# esq.net
KiCad netlist of a schematic drawn in Altium Designer
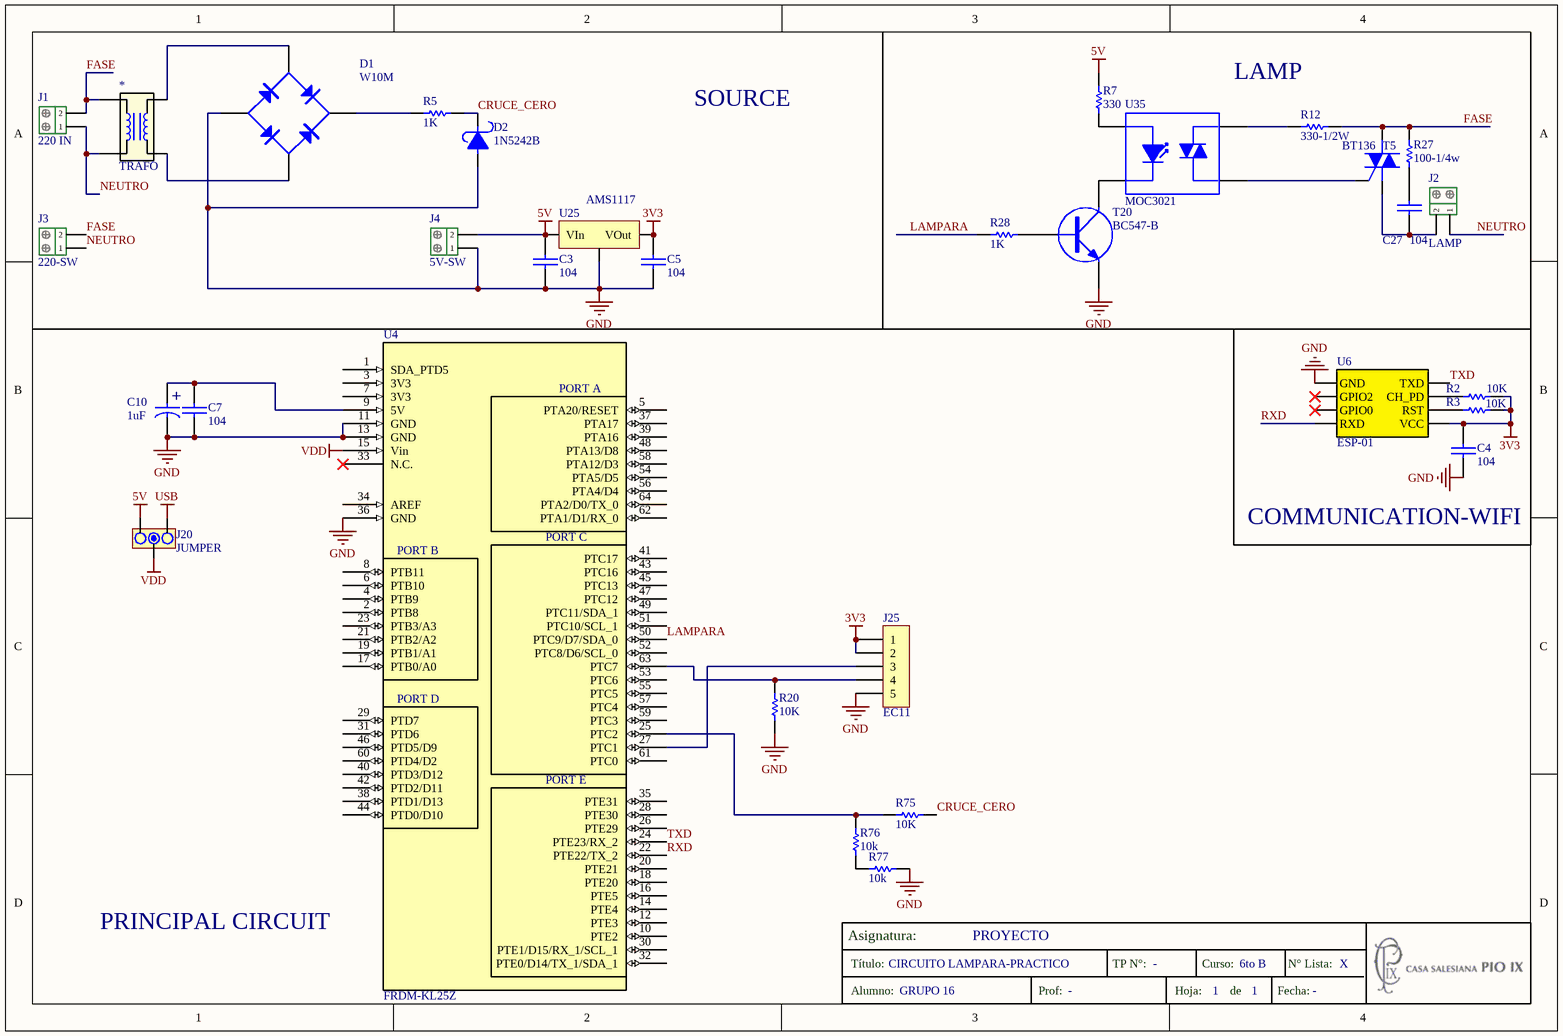
[diagram p0: esq.SchDoc]

(export (version "E")
  (design (tool "Eeschema 10.0.6"))
  (components
    (comp (ref "*") (value "TRAFO") (footprint "trafo") (libsource (lib "Schlib1") (part "TRAFO")))
    (comp (ref "C3")
      (value "104")
      (footprint "0805")
      (description "cap")
      (fields (field (name "AUTOR") "Guido Spataro"))
      (libsource (lib "Schlib1") (part "CAP"))
    )
    (comp (ref "C4")
      (value "104")
      (footprint "0805")
      (description "cap")
      (fields (field (name "AUTOR") "Guido Spataro"))
      (libsource (lib "scdlib") (part "CAP"))
    )
    (comp (ref "C5")
      (value "104")
      (footprint "0805")
      (description "cap")
      (fields (field (name "AUTOR") "Guido Spataro"))
      (libsource (lib "Schlib1") (part "CAP"))
    )
    (comp (ref "C7")
      (value "104")
      (footprint "0805")
      (description "cap")
      (fields (field (name "AUTOR") "Guido Spataro"))
      (libsource (lib "scdlib") (part "CAP"))
    )
    (comp (ref "C10")
      (value "1uF")
      (footprint "CAP100RP")
      (description "Cap polarizado")
      (libsource (lib "Schlib1") (part "CAPPOL"))
    )
    (comp (ref "C27")
      (value "104")
      (footprint "0805")
      (description "cap")
      (fields (field (name "AUTOR") "Guido Spataro"))
      (libsource (lib "Schlib1") (part "CAP"))
    )
    (comp (ref "D1") (value "W10M") (footprint "PUENTE - W10M") (libsource (lib "Schlib1") (part "PUENTE")))
    (comp (ref "D2")
      (value "1N5242B")
      (footprint "Diodo")
      (description "Diodo")
      (fields (field (name "AUTOR") "Guido Spataro"))
      (libsource (lib "Schlib1") (part "DIODO SCHOTTKY"))
    )
    (comp (ref "J1")
      (value "220 IN")
      (footprint "BORNERA2")
      (description "Bornera de 2 pines")
      (fields (field (name "AUTOR") "Guido Spataro"))
      (libsource (lib "Schlib1") (part "Bornera_2"))
    )
    (comp (ref "J2")
      (value "LAMP")
      (footprint "BORNERA2")
      (description "Bornera de 2 pines")
      (fields (field (name "AUTOR") "Guido Spataro"))
      (libsource (lib "") (part "Bornera_2_1"))
    )
    (comp (ref "J3")
      (value "220-SW")
      (footprint "BORNERA2")
      (description "Bornera de 2 pines")
      (fields (field (name "AUTOR") "Guido Spataro"))
      (libsource (lib "Schlib1") (part "Bornera_2"))
    )
    (comp (ref "J4")
      (value "5V-SW")
      (footprint "BORNERA2")
      (description "Bornera de 2 pines")
      (fields (field (name "AUTOR") "Guido Spataro"))
      (libsource (lib "Schlib1") (part "Bornera_2"))
    )
    (comp (ref "J20") (value "JUMPER") (footprint "JUMPER3") (libsource (lib "scdlib") (part "JUMPER3")))
    (comp (ref "J25") (value "EC11") (footprint "BORNERA5") (libsource (lib "Schlib1") (part "BORNERA 5")))
    (comp (ref "R2")
      (value "10K")
      (footprint "0805")
      (description "Resistencia")
      (fields (field (name "AUTOR") "Guido Spataro"))
      (libsource (lib "scdlib") (part "RES"))
    )
    (comp (ref "R3")
      (value "10K")
      (footprint "0805")
      (description "Resistencia")
      (fields (field (name "AUTOR") "Guido Spataro"))
      (libsource (lib "scdlib") (part "RES"))
    )
    (comp (ref "R5")
      (value "1K")
      (footprint "0805")
      (description "Resistencia")
      (fields (field (name "AUTOR") "Guido Spataro"))
      (libsource (lib "Schlib1") (part "RES"))
    )
    (comp (ref "R7")
      (value "330")
      (footprint "0805")
      (description "Resistencia")
      (fields (field (name "AUTOR") "Guido Spataro"))
      (libsource (lib "Schlib1") (part "RES"))
    )
    (comp (ref "R12")
      (value "330-1/2W")
      (footprint "RES500")
      (description "Resistencia")
      (fields (field (name "AUTOR") "Guido Spataro"))
      (libsource (lib "Schlib1") (part "RES"))
    )
    (comp (ref "R20")
      (value "10K")
      (footprint "0805")
      (description "Resistencia")
      (fields (field (name "AUTOR") "Guido Spataro"))
      (libsource (lib "Schlib1") (part "RES"))
    )
    (comp (ref "R27")
      (value "100-1/4w")
      (footprint "RES400")
      (description "Resistencia")
      (fields (field (name "AUTOR") "Guido Spataro"))
      (libsource (lib "Schlib1") (part "RES"))
    )
    (comp (ref "R28")
      (value "1K")
      (footprint "0805")
      (description "Resistencia")
      (fields (field (name "AUTOR") "Guido Spataro"))
      (libsource (lib "Schlib1") (part "RES"))
    )
    (comp (ref "R75")
      (value "10K")
      (footprint "0805")
      (description "Resistencia")
      (fields (field (name "AUTOR") "Guido Spataro"))
      (libsource (lib "Schlib1") (part "RES"))
    )
    (comp (ref "R76")
      (value "10k")
      (footprint "0805")
      (description "Resistencia")
      (fields (field (name "AUTOR") "Guido Spataro"))
      (libsource (lib "Schlib1") (part "RES"))
    )
    (comp (ref "R77")
      (value "10k")
      (footprint "0805")
      (description "Resistencia")
      (fields (field (name "AUTOR") "Guido Spataro"))
      (libsource (lib "Schlib1") (part "RES"))
    )
    (comp (ref "T5") (value "BT136") (footprint "BT136") (libsource (lib "Schlib1") (part "BT136")))
    (comp (ref "T20")
      (value "BC547-B")
      (footprint "SOT23")
      (libsource (lib "Schlib1") (part "TRANSISTOR NPN"))
    )
    (comp (ref "U4")
      (value "FRDM-KL25Z")
      (footprint "MICRO")
      (fields (field (name "AUTOR") "Guido Spataro"))
      (libsource (lib "Schlib1") (part "FRDM-KL25Z"))
    )
    (comp (ref "U6") (value "ESP-01") (footprint "ESP-01") (libsource (lib "Schlib1") (part "ESP-01")))
    (comp (ref "U25") (value "AMS1117") (footprint "AMS1117") (libsource (lib "Schlib1") (part "AMS1117")))
    (comp (ref "U35")
      (value "MOC3021")
      (footprint "MOC3021")
      (description "OPTO-ACOPLADOR")
      (libsource (lib "Schlib1") (part "MOC3021"))
    )
  )
  (nets
    (net (code "1") (name "/CRUCE_CERO") (class "Default")
      (node (ref "D2") (pin "2") (pinfunction "2_2") (pintype "passive"))
      (node (ref "R5") (pin "2") (pinfunction "2_2") (pintype "passive"))
      (node (ref "R75") (pin "1") (pinfunction "1_1") (pintype "passive"))
    )
    (net (code "2") (name "/FASE") (class "Default")
      (node (ref "*") (pin "1") (pinfunction "1_1") (pintype "passive"))
      (node (ref "J1") (pin "2") (pinfunction "2_2") (pintype "passive"))
      (node (ref "J3") (pin "2") (pinfunction "2_2") (pintype "passive"))
      (node (ref "R12") (pin "2") (pinfunction "2_2") (pintype "passive"))
      (node (ref "R27") (pin "2") (pinfunction "2_2") (pintype "passive"))
      (node (ref "T5") (pin "2") (pinfunction "M2_2") (pintype "passive"))
    )
    (net (code "3") (name "/LAMPARA") (class "Default")
      (node (ref "R28") (pin "1") (pinfunction "1_1") (pintype "passive"))
      (node (ref "U4") (pin "50") (pinfunction "PTC9/D7/SDA_0_50") (pintype "bidirectional"))
    )
    (net (code "4") (name "/NEUTRO") (class "Default")
      (node (ref "*") (pin "5") (pinfunction "5_5") (pintype "passive"))
      (node (ref "J1") (pin "1") (pinfunction "1_1") (pintype "passive"))
      (node (ref "J2") (pin "1") (pinfunction "1_1") (pintype "passive"))
      (node (ref "J3") (pin "1") (pinfunction "1_1") (pintype "passive"))
    )
    (net (code "5") (name "/RXD") (class "Default")
      (node (ref "U4") (pin "22") (pinfunction "PTE22/TX_2_22") (pintype "bidirectional"))
      (node (ref "U6") (pin "4") (pinfunction "RXD_4") (pintype "passive"))
    )
    (net (code "6") (name "/TXD") (class "Default")
      (node (ref "U4") (pin "24") (pinfunction "PTE23/RX_2_24") (pintype "bidirectional"))
      (node (ref "U6") (pin "5") (pinfunction "TXD_5") (pintype "passive"))
    )
    (net (code "7") (name "3V3") (class "Default")
      (node (ref "C4") (pin "2") (pinfunction "2_2") (pintype "passive"))
      (node (ref "C5") (pin "1") (pinfunction "1_1") (pintype "passive"))
      (node (ref "J25") (pin "1") (pinfunction "1_1") (pintype "passive"))
      (node (ref "J25") (pin "2") (pinfunction "2_2") (pintype "passive"))
      (node (ref "R2") (pin "1") (pinfunction "1_1") (pintype "passive"))
      (node (ref "R3") (pin "1") (pinfunction "1_1") (pintype "passive"))
      (node (ref "U25") (pin "3") (pinfunction "VOut_3") (pintype "passive"))
      (node (ref "U6") (pin "8") (pinfunction "VCC_8") (pintype "passive"))
    )
    (net (code "8") (name "5V") (class "Default")
      (node (ref "C3") (pin "1") (pinfunction "1_1") (pintype "passive"))
      (node (ref "J20") (pin "1") (pinfunction "1_1") (pintype "passive"))
      (node (ref "J4") (pin "2") (pinfunction "2_2") (pintype "passive"))
      (node (ref "R7") (pin "1") (pinfunction "1_1") (pintype "passive"))
      (node (ref "U25") (pin "1") (pinfunction "VIn_1") (pintype "passive"))
    )
    (net (code "9") (name "GND") (class "Default")
      (node (ref "C10") (pin "2") (pinfunction "2_2") (pintype "passive"))
      (node (ref "C3") (pin "2") (pinfunction "2_2") (pintype "passive"))
      (node (ref "C4") (pin "1") (pinfunction "1_1") (pintype "passive"))
      (node (ref "C5") (pin "2") (pinfunction "2_2") (pintype "passive"))
      (node (ref "C7") (pin "1") (pinfunction "1_1") (pintype "passive"))
      (node (ref "D1") (pin "3") (pinfunction "V-_3") (pintype "passive"))
      (node (ref "D2") (pin "1") (pinfunction "1_1") (pintype "passive"))
      (node (ref "J25") (pin "5") (pinfunction "5_5") (pintype "passive"))
      (node (ref "J4") (pin "1") (pinfunction "1_1") (pintype "passive"))
      (node (ref "R20") (pin "1") (pinfunction "1_1") (pintype "passive"))
      (node (ref "R77") (pin "1") (pinfunction "1_1") (pintype "passive"))
      (node (ref "T20") (pin "3") (pinfunction "E_3") (pintype "passive"))
      (node (ref "U25") (pin "2") (pinfunction "GND_2") (pintype "passive"))
      (node (ref "U4") (pin "11") (pinfunction "GND_11") (pintype "input"))
      (node (ref "U4") (pin "13") (pinfunction "GND_13") (pintype "input"))
      (node (ref "U4") (pin "36") (pinfunction "GND_36") (pintype "input"))
      (node (ref "U6") (pin "1") (pinfunction "GND_1") (pintype "passive"))
    )
    (net (code "10") (name "Net-(*-Pad7)") (class "Default")
      (node (ref "*") (pin "7") (pinfunction "7_7") (pintype "passive"))
      (node (ref "D1") (pin "2") (pinfunction "AC_2") (pintype "passive"))
    )
    (net (code "11") (name "Net-(*-Pad9)") (class "Default")
      (node (ref "*") (pin "9") (pinfunction "9_9") (pintype "passive"))
      (node (ref "D1") (pin "4") (pinfunction "AC_4") (pintype "passive"))
    )
    (net (code "12") (name "Net-(C27-Pad1)") (class "Default")
      (node (ref "C27") (pin "1") (pinfunction "1_1") (pintype "passive"))
      (node (ref "R27") (pin "1") (pinfunction "1_1") (pintype "passive"))
    )
    (net (code "13") (name "Net-(D1-V+)") (class "Default")
      (node (ref "D1") (pin "1") (pinfunction "V+_1") (pintype "passive"))
      (node (ref "R5") (pin "1") (pinfunction "1_1") (pintype "passive"))
    )
    (net (code "14") (name "Net-(R76-Pad1)") (class "Default")
      (node (ref "R76") (pin "1") (pinfunction "1_1") (pintype "passive"))
      (node (ref "R77") (pin "2") (pinfunction "2_2") (pintype "passive"))
    )
    (net (code "15") (name "Net-(T5-G)") (class "Default")
      (node (ref "T5") (pin "3") (pinfunction "G_3") (pintype "passive"))
      (node (ref "U35") (pin "4") (pinfunction "E_4") (pintype "passive"))
    )
    (net (code "16") (name "Net-(T5-M1)") (class "Default")
      (node (ref "C27") (pin "2") (pinfunction "2_2") (pintype "passive"))
      (node (ref "J2") (pin "2") (pinfunction "2_2") (pintype "passive"))
      (node (ref "T5") (pin "1") (pinfunction "M1_1") (pintype "passive"))
    )
    (net (code "17") (name "Net-(T20-B)") (class "Default")
      (node (ref "R28") (pin "2") (pinfunction "2_2") (pintype "passive"))
      (node (ref "T20") (pin "1") (pinfunction "B_1") (pintype "passive"))
    )
    (net (code "18") (name "Net-(T20-C)") (class "Default")
      (node (ref "T20") (pin "2") (pinfunction "C_2") (pintype "passive"))
      (node (ref "U35") (pin "2") (pinfunction "K_2") (pintype "passive"))
    )
    (net (code "19") (name "Net-(U4-5V)") (class "Default")
      (node (ref "C10") (pin "1") (pinfunction "1_1") (pintype "passive"))
      (node (ref "C7") (pin "2") (pinfunction "2_2") (pintype "passive"))
      (node (ref "U4") (pin "9") (pinfunction "5V_9") (pintype "input"))
    )
    (net (code "20") (name "Net-(U4-PTC1)") (class "Default")
      (node (ref "J25") (pin "3") (pinfunction "3_3") (pintype "passive"))
      (node (ref "U4") (pin "27") (pinfunction "PTC1_27") (pintype "bidirectional"))
    )
    (net (code "21") (name "Net-(U4-PTC2)") (class "Default")
      (node (ref "R75") (pin "2") (pinfunction "2_2") (pintype "passive"))
      (node (ref "R76") (pin "2") (pinfunction "2_2") (pintype "passive"))
      (node (ref "U4") (pin "25") (pinfunction "PTC2_25") (pintype "bidirectional"))
    )
    (net (code "22") (name "Net-(U4-PTC7)") (class "Default")
      (node (ref "J25") (pin "4") (pinfunction "4_4") (pintype "passive"))
      (node (ref "R20") (pin "2") (pinfunction "2_2") (pintype "passive"))
      (node (ref "U4") (pin "63") (pinfunction "PTC7_63") (pintype "bidirectional"))
    )
    (net (code "23") (name "Net-(U6-CH_PD)") (class "Default")
      (node (ref "R2") (pin "2") (pinfunction "2_2") (pintype "passive"))
      (node (ref "U6") (pin "6") (pinfunction "CH_PD_6") (pintype "passive"))
    )
    (net (code "24") (name "Net-(U6-RST)") (class "Default")
      (node (ref "R3") (pin "2") (pinfunction "2_2") (pintype "passive"))
      (node (ref "U6") (pin "7") (pinfunction "RST_7") (pintype "passive"))
    )
    (net (code "25") (name "Net-(U35-A)") (class "Default")
      (node (ref "R7") (pin "2") (pinfunction "2_2") (pintype "passive"))
      (node (ref "U35") (pin "1") (pinfunction "A_1") (pintype "passive"))
    )
    (net (code "26") (name "Net-(U35-C)") (class "Default")
      (node (ref "R12") (pin "1") (pinfunction "1_1") (pintype "passive"))
      (node (ref "U35") (pin "6") (pinfunction "C_6") (pintype "passive"))
    )
    (net (code "27") (name "USB") (class "Default")
      (node (ref "J20") (pin "3") (pinfunction "3_3") (pintype "passive"))
    )
    (net (code "28") (name "VDD") (class "Default")
      (node (ref "J20") (pin "2") (pinfunction "2_2") (pintype "passive"))
      (node (ref "U4") (pin "15") (pinfunction "Vin_15") (pintype "input"))
    )
    (net (code "29") (name "unconnected-(U4-3V3-Pad3)") (class "Default")
      (node (ref "U4") (pin "3") (pinfunction "3V3_3") (pintype "input"))
    )
    (net (code "30") (name "unconnected-(U4-3V3-Pad7)") (class "Default")
      (node (ref "U4") (pin "7") (pinfunction "3V3_7") (pintype "input"))
    )
    (net (code "31") (name "unconnected-(U4-AREF-Pad34)") (class "Default")
      (node (ref "U4") (pin "34") (pinfunction "AREF_34") (pintype "input"))
    )
    (net (code "32") (name "unconnected-(U4-N.C.-Pad33)") (class "Default")
      (node (ref "U4") (pin "33") (pinfunction "N.C._33") (pintype "open_emitter+no_connect"))
    )
    (net (code "33") (name "unconnected-(U4-PTA1{slash}D1{slash}RX_0-Pad62)") (class "Default")
      (node (ref "U4") (pin "62") (pinfunction "PTA1/D1/RX_0_62") (pintype "bidirectional"))
    )
    (net (code "34") (name "unconnected-(U4-PTA2{slash}D0{slash}TX_0-Pad64)") (class "Default")
      (node (ref "U4") (pin "64") (pinfunction "PTA2/D0/TX_0_64") (pintype "bidirectional"))
    )
    (net (code "35") (name "unconnected-(U4-PTA4{slash}D4-Pad56)") (class "Default")
      (node (ref "U4") (pin "56") (pinfunction "PTA4/D4_56") (pintype "bidirectional"))
    )
    (net (code "36") (name "unconnected-(U4-PTA5{slash}D5-Pad54)") (class "Default")
      (node (ref "U4") (pin "54") (pinfunction "PTA5/D5_54") (pintype "bidirectional"))
    )
    (net (code "37") (name "unconnected-(U4-PTA12{slash}D3-Pad58)") (class "Default")
      (node (ref "U4") (pin "58") (pinfunction "PTA12/D3_58") (pintype "bidirectional"))
    )
    (net (code "38") (name "unconnected-(U4-PTA13{slash}D8-Pad48)") (class "Default")
      (node (ref "U4") (pin "48") (pinfunction "PTA13/D8_48") (pintype "bidirectional"))
    )
    (net (code "39") (name "unconnected-(U4-PTA16-Pad39)") (class "Default")
      (node (ref "U4") (pin "39") (pinfunction "PTA16_39") (pintype "bidirectional"))
    )
    (net (code "40") (name "unconnected-(U4-PTA17-Pad37)") (class "Default")
      (node (ref "U4") (pin "37") (pinfunction "PTA17_37") (pintype "bidirectional"))
    )
    (net (code "41") (name "unconnected-(U4-PTA20{slash}RESET-Pad5)") (class "Default")
      (node (ref "U4") (pin "5") (pinfunction "PTA20/RESET_5") (pintype "bidirectional"))
    )
    (net (code "42") (name "unconnected-(U4-PTB0{slash}A0-Pad17)") (class "Default")
      (node (ref "U4") (pin "17") (pinfunction "PTB0/A0_17") (pintype "bidirectional"))
    )
    (net (code "43") (name "unconnected-(U4-PTB1{slash}A1-Pad19)") (class "Default")
      (node (ref "U4") (pin "19") (pinfunction "PTB1/A1_19") (pintype "bidirectional"))
    )
    (net (code "44") (name "unconnected-(U4-PTB2{slash}A2-Pad21)") (class "Default")
      (node (ref "U4") (pin "21") (pinfunction "PTB2/A2_21") (pintype "bidirectional"))
    )
    (net (code "45") (name "unconnected-(U4-PTB3{slash}A3-Pad23)") (class "Default")
      (node (ref "U4") (pin "23") (pinfunction "PTB3/A3_23") (pintype "bidirectional"))
    )
    (net (code "46") (name "unconnected-(U4-PTB8-Pad2)") (class "Default")
      (node (ref "U4") (pin "2") (pinfunction "PTB8_2") (pintype "bidirectional"))
    )
    (net (code "47") (name "unconnected-(U4-PTB9-Pad4)") (class "Default")
      (node (ref "U4") (pin "4") (pinfunction "PTB9_4") (pintype "bidirectional"))
    )
    (net (code "48") (name "unconnected-(U4-PTB10-Pad6)") (class "Default")
      (node (ref "U4") (pin "6") (pinfunction "PTB10_6") (pintype "bidirectional"))
    )
    (net (code "49") (name "unconnected-(U4-PTB11-Pad8)") (class "Default")
      (node (ref "U4") (pin "8") (pinfunction "PTB11_8") (pintype "bidirectional"))
    )
    (net (code "50") (name "unconnected-(U4-PTC0-Pad61)") (class "Default")
      (node (ref "U4") (pin "61") (pinfunction "PTC0_61") (pintype "bidirectional"))
    )
    (net (code "51") (name "unconnected-(U4-PTC3-Pad59)") (class "Default")
      (node (ref "U4") (pin "59") (pinfunction "PTC3_59") (pintype "bidirectional"))
    )
    (net (code "52") (name "unconnected-(U4-PTC4-Pad57)") (class "Default")
      (node (ref "U4") (pin "57") (pinfunction "PTC4_57") (pintype "bidirectional"))
    )
    (net (code "53") (name "unconnected-(U4-PTC5-Pad55)") (class "Default")
      (node (ref "U4") (pin "55") (pinfunction "PTC5_55") (pintype "bidirectional"))
    )
    (net (code "54") (name "unconnected-(U4-PTC6-Pad53)") (class "Default")
      (node (ref "U4") (pin "53") (pinfunction "PTC6_53") (pintype "bidirectional"))
    )
    (net (code "55") (name "unconnected-(U4-PTC8{slash}D6{slash}SCL_0-Pad52)") (class "Default")
      (node (ref "U4") (pin "52") (pinfunction "PTC8/D6/SCL_0_52") (pintype "bidirectional"))
    )
    (net (code "56") (name "unconnected-(U4-PTC10{slash}SCL_1-Pad51)") (class "Default")
      (node (ref "U4") (pin "51") (pinfunction "PTC10/SCL_1_51") (pintype "bidirectional"))
    )
    (net (code "57") (name "unconnected-(U4-PTC11{slash}SDA_1-Pad49)") (class "Default")
      (node (ref "U4") (pin "49") (pinfunction "PTC11/SDA_1_49") (pintype "bidirectional"))
    )
    (net (code "58") (name "unconnected-(U4-PTC12-Pad47)") (class "Default")
      (node (ref "U4") (pin "47") (pinfunction "PTC12_47") (pintype "bidirectional"))
    )
    (net (code "59") (name "unconnected-(U4-PTC13-Pad45)") (class "Default")
      (node (ref "U4") (pin "45") (pinfunction "PTC13_45") (pintype "bidirectional"))
    )
    (net (code "60") (name "unconnected-(U4-PTC16-Pad43)") (class "Default")
      (node (ref "U4") (pin "43") (pinfunction "PTC16_43") (pintype "bidirectional"))
    )
    (net (code "61") (name "unconnected-(U4-PTC17-Pad41)") (class "Default")
      (node (ref "U4") (pin "41") (pinfunction "PTC17_41") (pintype "bidirectional"))
    )
    (net (code "62") (name "unconnected-(U4-PTD0{slash}D10-Pad44)") (class "Default")
      (node (ref "U4") (pin "44") (pinfunction "PTD0/D10_44") (pintype "bidirectional"))
    )
    (net (code "63") (name "unconnected-(U4-PTD1{slash}D13-Pad38)") (class "Default")
      (node (ref "U4") (pin "38") (pinfunction "PTD1/D13_38") (pintype "bidirectional"))
    )
    (net (code "64") (name "unconnected-(U4-PTD2{slash}D11-Pad42)") (class "Default")
      (node (ref "U4") (pin "42") (pinfunction "PTD2/D11_42") (pintype "bidirectional"))
    )
    (net (code "65") (name "unconnected-(U4-PTD3{slash}D12-Pad40)") (class "Default")
      (node (ref "U4") (pin "40") (pinfunction "PTD3/D12_40") (pintype "bidirectional"))
    )
    (net (code "66") (name "unconnected-(U4-PTD4{slash}D2-Pad60)") (class "Default")
      (node (ref "U4") (pin "60") (pinfunction "PTD4/D2_60") (pintype "bidirectional"))
    )
    (net (code "67") (name "unconnected-(U4-PTD5{slash}D9-Pad46)") (class "Default")
      (node (ref "U4") (pin "46") (pinfunction "PTD5/D9_46") (pintype "bidirectional"))
    )
    (net (code "68") (name "unconnected-(U4-PTD6-Pad31)") (class "Default")
      (node (ref "U4") (pin "31") (pinfunction "PTD6_31") (pintype "bidirectional"))
    )
    (net (code "69") (name "unconnected-(U4-PTD7-Pad29)") (class "Default")
      (node (ref "U4") (pin "29") (pinfunction "PTD7_29") (pintype "bidirectional"))
    )
    (net (code "70") (name "unconnected-(U4-PTE0{slash}D14{slash}TX_1{slash}SDA_1-Pad32)") (class "Default")
      (node (ref "U4") (pin "32") (pinfunction "PTE0/D14/TX_1/SDA_1_32") (pintype "bidirectional"))
    )
    (net (code "71") (name "unconnected-(U4-PTE1{slash}D15{slash}RX_1{slash}SCL_1-Pad30)") (class "Default")
      (node (ref "U4") (pin "30") (pinfunction "PTE1/D15/RX_1/SCL_1_30") (pintype "bidirectional"))
    )
    (net (code "72") (name "unconnected-(U4-PTE2-Pad10)") (class "Default")
      (node (ref "U4") (pin "10") (pinfunction "PTE2_10") (pintype "bidirectional"))
    )
    (net (code "73") (name "unconnected-(U4-PTE3-Pad12)") (class "Default")
      (node (ref "U4") (pin "12") (pinfunction "PTE3_12") (pintype "bidirectional"))
    )
    (net (code "74") (name "unconnected-(U4-PTE4-Pad14)") (class "Default")
      (node (ref "U4") (pin "14") (pinfunction "PTE4_14") (pintype "bidirectional"))
    )
    (net (code "75") (name "unconnected-(U4-PTE5-Pad16)") (class "Default")
      (node (ref "U4") (pin "16") (pinfunction "PTE5_16") (pintype "bidirectional"))
    )
    (net (code "76") (name "unconnected-(U4-PTE20-Pad18)") (class "Default")
      (node (ref "U4") (pin "18") (pinfunction "PTE20_18") (pintype "bidirectional"))
    )
    (net (code "77") (name "unconnected-(U4-PTE21-Pad20)") (class "Default")
      (node (ref "U4") (pin "20") (pinfunction "PTE21_20") (pintype "bidirectional"))
    )
    (net (code "78") (name "unconnected-(U4-PTE29-Pad26)") (class "Default")
      (node (ref "U4") (pin "26") (pinfunction "PTE29_26") (pintype "bidirectional"))
    )
    (net (code "79") (name "unconnected-(U4-PTE30-Pad28)") (class "Default")
      (node (ref "U4") (pin "28") (pinfunction "PTE30_28") (pintype "bidirectional"))
    )
    (net (code "80") (name "unconnected-(U4-PTE31-Pad35)") (class "Default")
      (node (ref "U4") (pin "35") (pinfunction "PTE31_35") (pintype "bidirectional"))
    )
    (net (code "81") (name "unconnected-(U4-SDA_PTD5-Pad1)") (class "Default")
      (node (ref "U4") (pin "1") (pinfunction "SDA_PTD5_1") (pintype "input"))
    )
    (net (code "82") (name "unconnected-(U6-GPIO0-Pad3)") (class "Default")
      (node (ref "U6") (pin "3") (pinfunction "GPIO0_3") (pintype "passive+no_connect"))
    )
    (net (code "83") (name "unconnected-(U6-GPIO2-Pad2)") (class "Default")
      (node (ref "U6") (pin "2") (pinfunction "GPIO2_2") (pintype "passive+no_connect"))
    )
  )
)
